# impulse.net
KiCad netlist of a schematic drawn in EAGLE
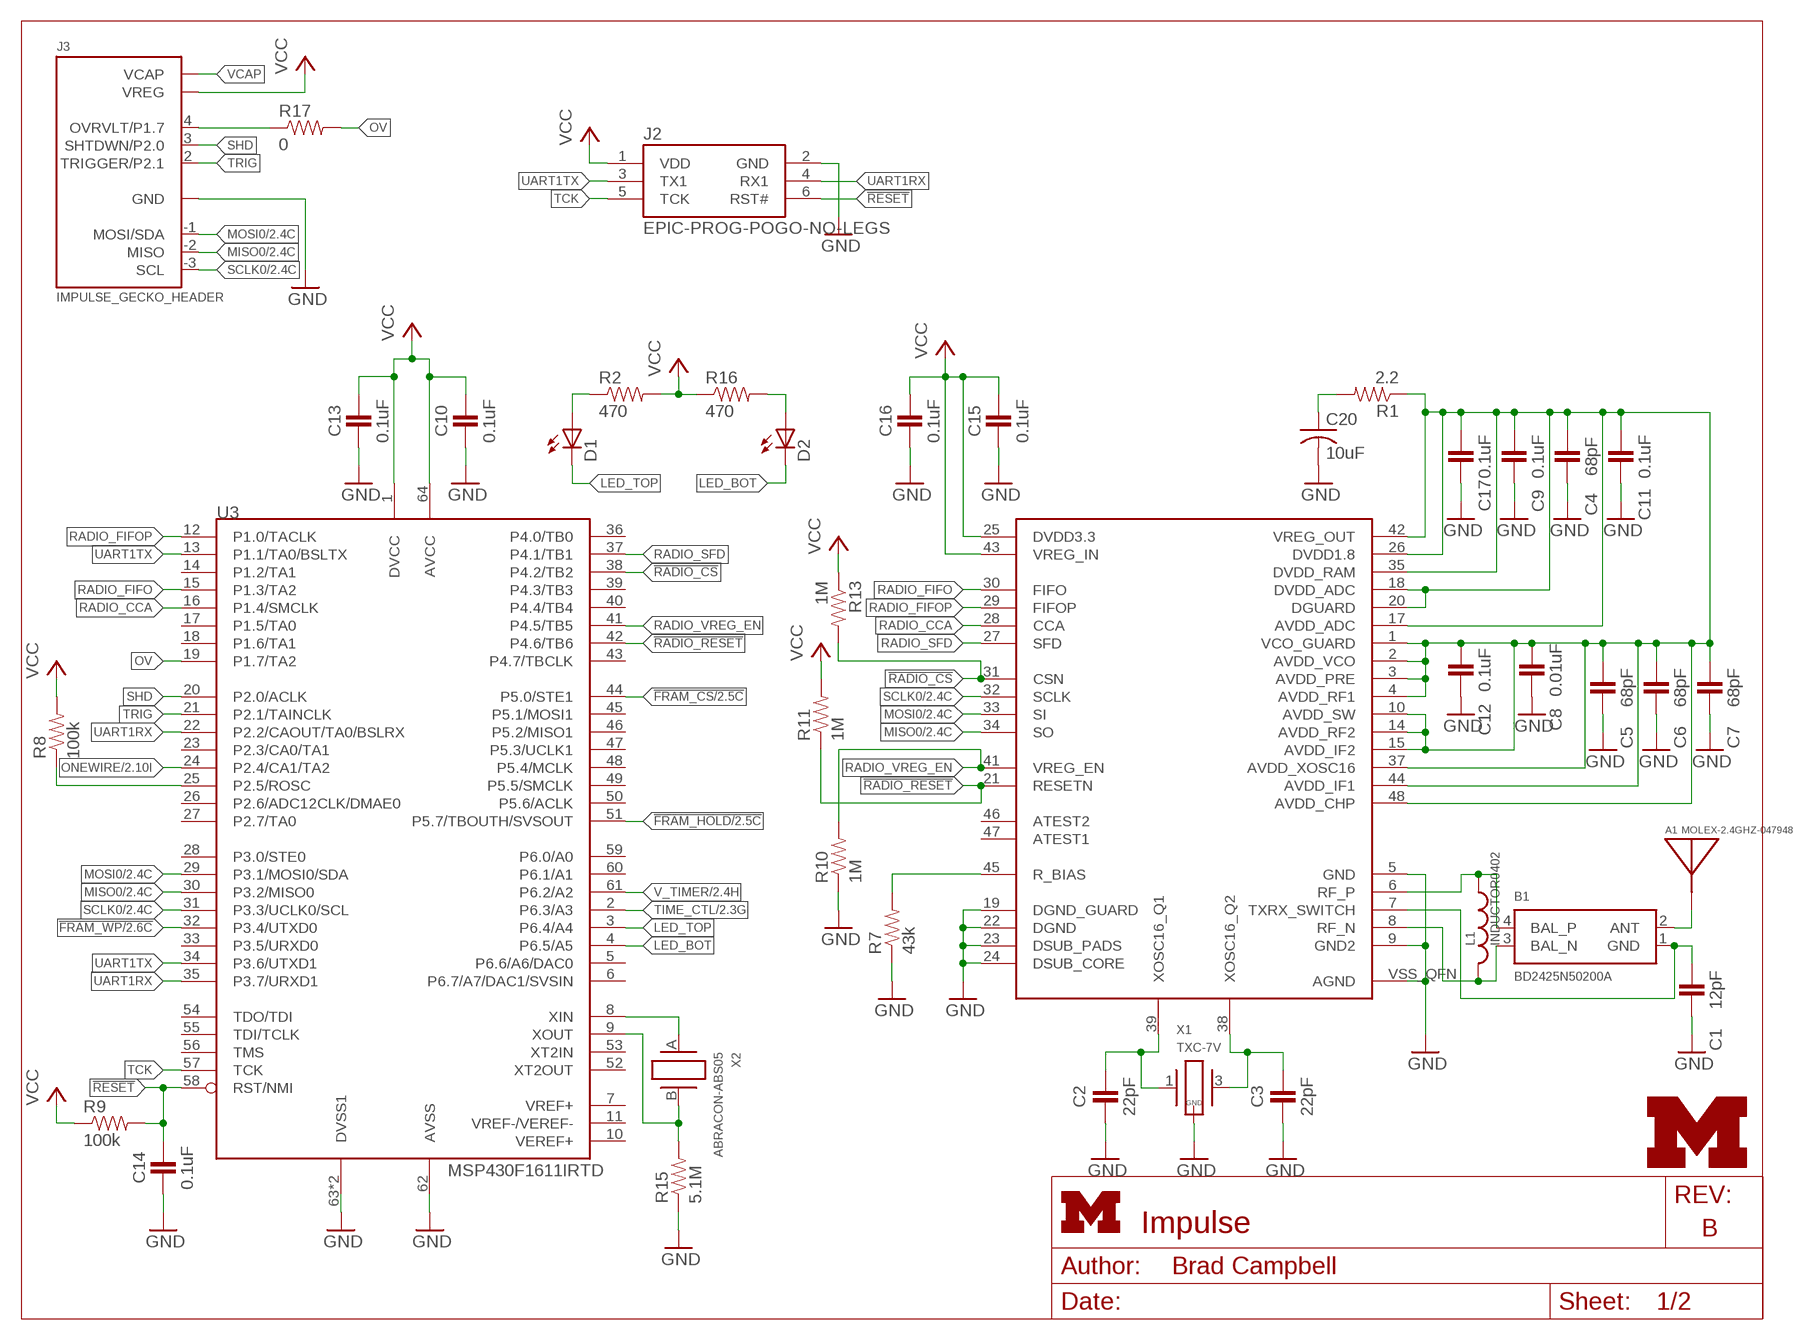
[diagram p0: schematic, sheet 1]
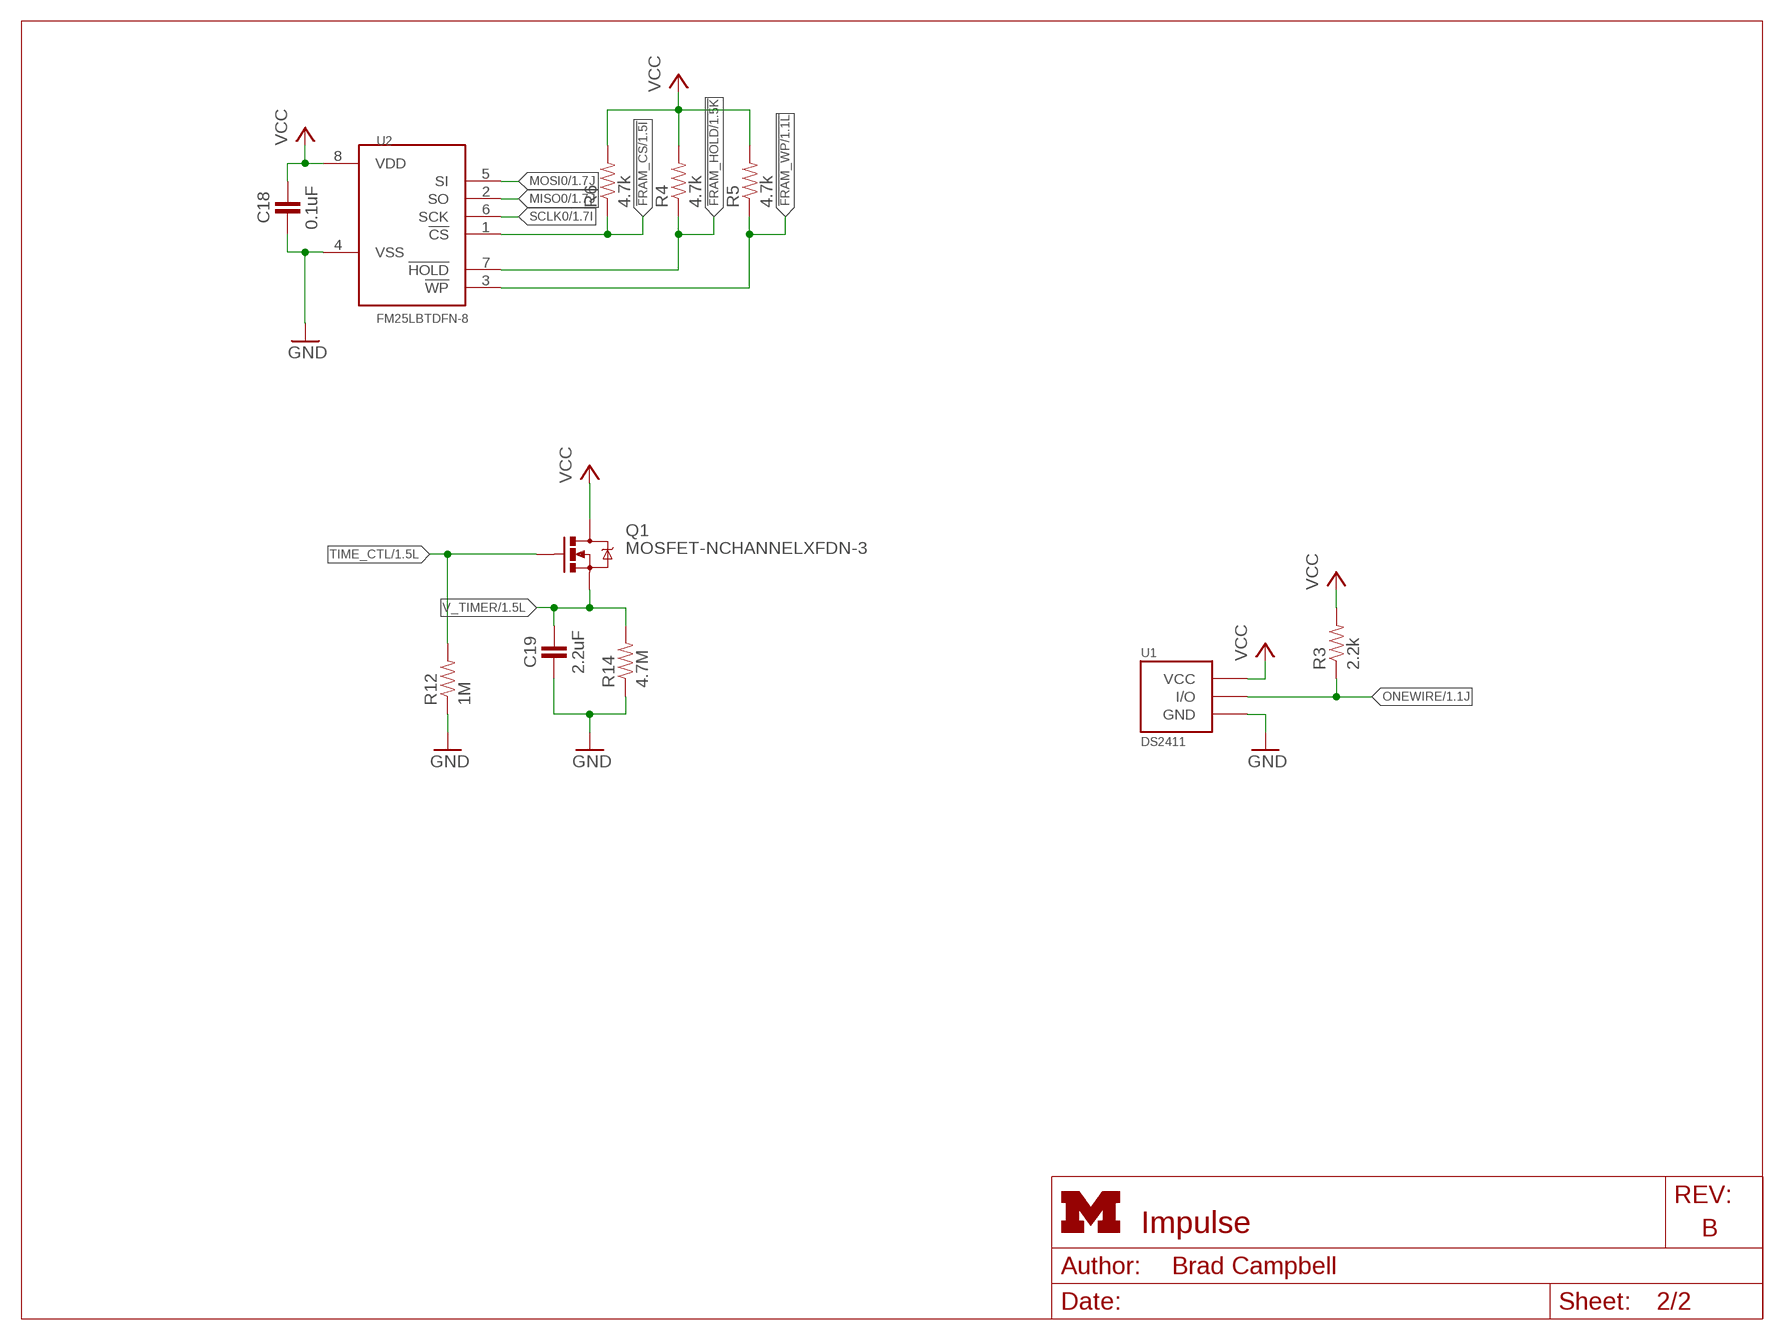
[diagram p1: schematic, sheet 2]

(export (version "E")
  (design (tool "Eeschema 10.0.6"))
  (components
    (comp (ref "C18")
      (value "0.1uF")
      (footprint "eagle-import:0402_CAP")
      (libsource (lib "eagle-import") (part "CAPACITOR"))
    )
    (comp (ref "C19")
      (value "2.2uF")
      (footprint "eagle-import:0402_CAP")
      (libsource (lib "eagle-import") (part "CAPACITOR"))
    )
    (comp (ref "Q1")
      (value "MOSFET-NCHANNELXFDN-3")
      (footprint "eagle-import:XFDFN-3")
      (libsource (lib "eagle-import") (part "MOSFET-NCHANNELXFDN-3"))
    )
    (comp (ref "R3")
      (value "2.2k")
      (footprint "eagle-import:0402_RES")
      (libsource (lib "eagle-import") (part "RESISTOR"))
    )
    (comp (ref "R4")
      (value "4.7k")
      (footprint "eagle-import:0402_RES")
      (libsource (lib "eagle-import") (part "RESISTOR"))
    )
    (comp (ref "R5")
      (value "4.7k")
      (footprint "eagle-import:0402_RES")
      (libsource (lib "eagle-import") (part "RESISTOR"))
    )
    (comp (ref "R6")
      (value "4.7k")
      (footprint "eagle-import:0402_RES")
      (libsource (lib "eagle-import") (part "RESISTOR"))
    )
    (comp (ref "R12")
      (value "1M")
      (footprint "eagle-import:0402_RES")
      (libsource (lib "eagle-import") (part "RESISTOR"))
    )
    (comp (ref "R14")
      (value "4.7M")
      (footprint "eagle-import:0402_RES")
      (libsource (lib "eagle-import") (part "RESISTOR"))
    )
    (comp (ref "U1")
      (value "DS2411")
      (footprint "eagle-import:SOT-23")
      (libsource (lib "eagle-import") (part "DS2411"))
    )
    (comp (ref "U2")
      (value "FM25LBTDFN-8")
      (footprint "eagle-import:TDFN-8")
      (libsource (lib "eagle-import") (part "FM25LBTDFN-8"))
    )
    (comp (ref "A1")
      (value "MOLEX-2.4GHZ-047948")
      (footprint "eagle-import:MOLEX-47948-ANTENNA")
      (libsource (lib "eagle-import") (part "MOLEX-2.4GHZ-047948"))
    )
    (comp (ref "B1")
      (value "BD2425N50200A")
      (footprint "eagle-import:BD2425N50200A")
      (libsource (lib "eagle-import") (part "BD2425N50200A"))
    )
    (comp (ref "C1")
      (value "12pF")
      (footprint "eagle-import:0402_CAP")
      (libsource (lib "eagle-import") (part "CAPACITOR"))
    )
    (comp (ref "C2")
      (value "22pF")
      (footprint "eagle-import:0402_CAP")
      (libsource (lib "eagle-import") (part "CAPACITOR"))
    )
    (comp (ref "C3")
      (value "22pF")
      (footprint "eagle-import:0402_CAP")
      (libsource (lib "eagle-import") (part "CAPACITOR"))
    )
    (comp (ref "C4")
      (value "68pF")
      (footprint "eagle-import:0402_CAP")
      (libsource (lib "eagle-import") (part "CAPACITOR"))
    )
    (comp (ref "C5")
      (value "68pF")
      (footprint "eagle-import:0402_CAP")
      (libsource (lib "eagle-import") (part "CAPACITOR"))
    )
    (comp (ref "C6")
      (value "68pF")
      (footprint "eagle-import:0402_CAP")
      (libsource (lib "eagle-import") (part "CAPACITOR"))
    )
    (comp (ref "C7")
      (value "68pF")
      (footprint "eagle-import:0402_CAP")
      (libsource (lib "eagle-import") (part "CAPACITOR"))
    )
    (comp (ref "C8")
      (value "0.01uF")
      (footprint "eagle-import:0402_CAP")
      (libsource (lib "eagle-import") (part "CAPACITOR"))
    )
    (comp (ref "C9")
      (value "0.1uF")
      (footprint "eagle-import:0402_CAP")
      (libsource (lib "eagle-import") (part "CAPACITOR"))
    )
    (comp (ref "C10")
      (value "0.1uF")
      (footprint "eagle-import:0402_CAP")
      (libsource (lib "eagle-import") (part "CAPACITOR"))
    )
    (comp (ref "C11")
      (value "0.1uF")
      (footprint "eagle-import:0402_CAP")
      (libsource (lib "eagle-import") (part "CAPACITOR"))
    )
    (comp (ref "C12")
      (value "0.1uF")
      (footprint "eagle-import:0402_CAP")
      (libsource (lib "eagle-import") (part "CAPACITOR"))
    )
    (comp (ref "C13")
      (value "0.1uF")
      (footprint "eagle-import:0402_CAP")
      (libsource (lib "eagle-import") (part "CAPACITOR"))
    )
    (comp (ref "C14")
      (value "0.1uF")
      (footprint "eagle-import:0402_CAP")
      (libsource (lib "eagle-import") (part "CAPACITOR"))
    )
    (comp (ref "C15")
      (value "0.1uF")
      (footprint "eagle-import:0402_CAP")
      (libsource (lib "eagle-import") (part "CAPACITOR"))
    )
    (comp (ref "C16")
      (value "0.1uF")
      (footprint "eagle-import:0402_CAP")
      (libsource (lib "eagle-import") (part "CAPACITOR"))
    )
    (comp (ref "C17")
      (value "0.1uF")
      (footprint "eagle-import:0402_CAP")
      (libsource (lib "eagle-import") (part "CAPACITOR"))
    )
    (comp (ref "C20")
      (value "10uF")
      (footprint "eagle-import:C0805")
      (libsource (lib "eagle-import") (part "C-USC0805"))
    )
    (comp (ref "D1")
      (value "LED0603")
      (footprint "eagle-import:LED-0603")
      (libsource (lib "eagle-import") (part "LED0603"))
    )
    (comp (ref "D2")
      (value "LED0603")
      (footprint "eagle-import:LED-0603")
      (libsource (lib "eagle-import") (part "LED0603"))
    )
    (comp (ref "J2")
      (value "EPIC-PROG-POGO-NO-LEGS")
      (footprint "eagle-import:TC2030-IDC-NL")
      (libsource (lib "eagle-import") (part "EPIC-PROG-POGO-NO-LEGS"))
    )
    (comp (ref "J3")
      (value "IMPULSE_GECKO_HEADER")
      (footprint "eagle-import:HEADER1X9_0.05IN")
      (libsource (lib "eagle-import") (part "IMPULSE_GECKO_HEADER"))
    )
    (comp (ref "L1")
      (value "INDUCTOR0402")
      (footprint "eagle-import:0402_CAP")
      (libsource (lib "eagle-import") (part "INDUCTOR0402"))
    )
    (comp (ref "R1")
      (value "2.2")
      (footprint "eagle-import:0402_RES")
      (libsource (lib "eagle-import") (part "RESISTOR"))
    )
    (comp (ref "R2")
      (value "470")
      (footprint "eagle-import:0402_RES")
      (libsource (lib "eagle-import") (part "RESISTOR"))
    )
    (comp (ref "R7")
      (value "43k")
      (footprint "eagle-import:0402_RES")
      (libsource (lib "eagle-import") (part "RESISTOR"))
    )
    (comp (ref "R8")
      (value "100k")
      (footprint "eagle-import:0402_RES")
      (libsource (lib "eagle-import") (part "RESISTOR"))
    )
    (comp (ref "R9")
      (value "100k")
      (footprint "eagle-import:0402_RES")
      (libsource (lib "eagle-import") (part "RESISTOR"))
    )
    (comp (ref "R10")
      (value "1M")
      (footprint "eagle-import:0402_RES")
      (libsource (lib "eagle-import") (part "RESISTOR"))
    )
    (comp (ref "R11")
      (value "1M")
      (footprint "eagle-import:0402_RES")
      (libsource (lib "eagle-import") (part "RESISTOR"))
    )
    (comp (ref "R13")
      (value "1M")
      (footprint "eagle-import:0402_RES")
      (libsource (lib "eagle-import") (part "RESISTOR"))
    )
    (comp (ref "R15")
      (value "5.1M")
      (footprint "eagle-import:0402_RES")
      (libsource (lib "eagle-import") (part "RESISTOR"))
    )
    (comp (ref "R16")
      (value "470")
      (footprint "eagle-import:0402_RES")
      (libsource (lib "eagle-import") (part "RESISTOR"))
    )
    (comp (ref "R17")
      (value "0")
      (footprint "eagle-import:0402_RES")
      (libsource (lib "eagle-import") (part "RESISTOR"))
    )
    (comp (ref "U$1")
      (value "UMICH_SOLID_SMALL")
      (footprint "eagle-import:UMICH_SOLID_75MIL")
      (libsource (lib "eagle-import") (part "UMICH_SOLID_SMALL"))
    )
    (comp (ref "U3")
      (value "MSP430F1611IRTD")
      (footprint "eagle-import:S-PVQFN-N64")
      (libsource (lib "eagle-import") (part "MSP430F1611IRTD"))
    )
    (comp (ref "U4")
      (value "CC2420RGZ")
      (footprint "eagle-import:S-PVQFN-N48")
      (libsource (lib "eagle-import") (part "CC2420RGZ"))
    )
    (comp (ref "X1")
      (value "TXC-7V")
      (footprint "eagle-import:TXC-7V")
      (libsource (lib "eagle-import") (part "TXC-7V"))
    )
    (comp (ref "X2")
      (value "ABRACON-ABS05")
      (footprint "eagle-import:ABS05")
      (libsource (lib "eagle-import") (part "ABRACON-ABS05"))
    )
  )
  (nets
    (net (code "1") (name "GND") (class "Default")
      (node (ref "C1") (pin "2") (pinfunction "2_2") (pintype "bidirectional"))
      (node (ref "C10") (pin "2") (pinfunction "2_2") (pintype "bidirectional"))
      (node (ref "C11") (pin "2") (pinfunction "2_2") (pintype "bidirectional"))
      (node (ref "C12") (pin "2") (pinfunction "2_2") (pintype "bidirectional"))
      (node (ref "C13") (pin "2") (pinfunction "2_2") (pintype "bidirectional"))
      (node (ref "C14") (pin "2") (pinfunction "2_2") (pintype "bidirectional"))
      (node (ref "C15") (pin "2") (pinfunction "2_2") (pintype "bidirectional"))
      (node (ref "C16") (pin "2") (pinfunction "2_2") (pintype "bidirectional"))
      (node (ref "C17") (pin "2") (pinfunction "2_2") (pintype "bidirectional"))
      (node (ref "C18") (pin "2") (pinfunction "2_2") (pintype "bidirectional"))
      (node (ref "C19") (pin "2") (pinfunction "2_2") (pintype "bidirectional"))
      (node (ref "C2") (pin "2") (pinfunction "2_2") (pintype "bidirectional"))
      (node (ref "C20") (pin "2") (pinfunction "2_2") (pintype "passive"))
      (node (ref "C3") (pin "2") (pinfunction "2_2") (pintype "bidirectional"))
      (node (ref "C4") (pin "2") (pinfunction "2_2") (pintype "bidirectional"))
      (node (ref "C5") (pin "2") (pinfunction "2_2") (pintype "bidirectional"))
      (node (ref "C6") (pin "2") (pinfunction "2_2") (pintype "bidirectional"))
      (node (ref "C7") (pin "2") (pinfunction "2_2") (pintype "bidirectional"))
      (node (ref "C8") (pin "2") (pinfunction "2_2") (pintype "bidirectional"))
      (node (ref "C9") (pin "2") (pinfunction "2_2") (pintype "bidirectional"))
      (node (ref "J2") (pin "2") (pinfunction "GND_2") (pintype "bidirectional"))
      (node (ref "J3") (pin "0") (pinfunction "GND_0") (pintype "bidirectional"))
      (node (ref "R10") (pin "1") (pinfunction "1_1") (pintype "passive"))
      (node (ref "R12") (pin "1") (pinfunction "1_1") (pintype "passive"))
      (node (ref "R14") (pin "1") (pinfunction "1_1") (pintype "passive"))
      (node (ref "R15") (pin "1") (pinfunction "1_1") (pintype "passive"))
      (node (ref "R7") (pin "1") (pinfunction "1_1") (pintype "passive"))
      (node (ref "U1") (pin "3") (pinfunction "GND_3") (pintype "bidirectional"))
      (node (ref "U2") (pin "4") (pinfunction "VSS_4") (pintype "bidirectional"))
      (node (ref "U3") (pin "62") (pinfunction "AVSS_62") (pintype "power_in"))
      (node (ref "U3") (pin "63") (pinfunction "DVSS1_63") (pintype "power_in"))
      (node (ref "U3") (pin "GND") (pinfunction "DVSS1_GND") (pintype "power_in"))
      (node (ref "U4") (pin "19") (pinfunction "DGND_GUARD_19") (pintype "bidirectional"))
      (node (ref "U4") (pin "22") (pinfunction "DGND_22") (pintype "bidirectional"))
      (node (ref "U4") (pin "23") (pinfunction "DSUB_PADS_23") (pintype "bidirectional"))
      (node (ref "U4") (pin "24") (pinfunction "DSUB_CORE_24") (pintype "bidirectional"))
      (node (ref "U4") (pin "5") (pinfunction "GND_5") (pintype "bidirectional"))
      (node (ref "U4") (pin "9") (pinfunction "GND2_9") (pintype "bidirectional"))
      (node (ref "U4") (pin "VSS_QFN") (pinfunction "AGND_VSS_QFN") (pintype "bidirectional"))
      (node (ref "X1") (pin "2") (pinfunction "GND_2") (pintype "bidirectional"))
      (node (ref "X1") (pin "4") (pinfunction "GND_4") (pintype "bidirectional"))
    )
    (net (code "2") (name "LED_BOT") (class "Default")
      (node (ref "D2") (pin "C") (pinfunction "C_C") (pintype "passive"))
      (node (ref "U3") (pin "4") (pinfunction "P6.5/A5_4") (pintype "bidirectional"))
    )
    (net (code "3") (name "LED_TOP") (class "Default")
      (node (ref "D1") (pin "C") (pinfunction "C_C") (pintype "passive"))
      (node (ref "U3") (pin "3") (pinfunction "P6.4/A4_3") (pintype "bidirectional"))
    )
    (net (code "4") (name "MISO0") (class "Default")
      (node (ref "J3") (pin "-2") (pinfunction "MISO_-2") (pintype "bidirectional"))
      (node (ref "U2") (pin "2") (pinfunction "SO_2") (pintype "bidirectional"))
      (node (ref "U3") (pin "30") (pinfunction "P3.2/MISO0_30") (pintype "bidirectional"))
      (node (ref "U4") (pin "34") (pinfunction "SO_34") (pintype "bidirectional"))
    )
    (net (code "5") (name "MOSI0") (class "Default")
      (node (ref "J3") (pin "-1") (pinfunction "MOSI/SDA_-1") (pintype "bidirectional"))
      (node (ref "U2") (pin "5") (pinfunction "SI_5") (pintype "bidirectional"))
      (node (ref "U3") (pin "29") (pinfunction "P3.1/MOSI0/SDA_29") (pintype "bidirectional"))
      (node (ref "U4") (pin "33") (pinfunction "SI_33") (pintype "bidirectional"))
    )
    (net (code "6") (name "Net-(A1-ANTENNA)") (class "Default")
      (node (ref "A1") (pin "1") (pinfunction "ANTENNA_1") (pintype "bidirectional"))
      (node (ref "B1") (pin "2") (pinfunction "ANT_2") (pintype "bidirectional"))
    )
    (net (code "7") (name "Net-(B1-BAL_N)") (class "Default")
      (node (ref "B1") (pin "3") (pinfunction "BAL_N_3") (pintype "bidirectional"))
      (node (ref "L1") (pin "2") (pinfunction "P$2_2") (pintype "bidirectional"))
      (node (ref "U4") (pin "8") (pinfunction "RF_N_8") (pintype "bidirectional"))
    )
    (net (code "8") (name "Net-(B1-BAL_P)") (class "Default")
      (node (ref "B1") (pin "4") (pinfunction "BAL_P_4") (pintype "bidirectional"))
      (node (ref "L1") (pin "1") (pinfunction "1_1") (pintype "bidirectional"))
      (node (ref "U4") (pin "6") (pinfunction "RF_P_6") (pintype "bidirectional"))
    )
    (net (code "9") (name "Net-(B1-GND)") (class "Default")
      (node (ref "B1") (pin "1") (pinfunction "GND_1") (pintype "bidirectional"))
      (node (ref "C1") (pin "1") (pinfunction "1_1") (pintype "bidirectional"))
      (node (ref "U4") (pin "7") (pinfunction "TXRX_SWITCH_7") (pintype "bidirectional"))
    )
    (net (code "10") (name "Net-(C20-Pad1)") (class "Default")
      (node (ref "C20") (pin "1") (pinfunction "1_1") (pintype "passive"))
      (node (ref "R1") (pin "2") (pinfunction "2_2") (pintype "passive"))
    )
    (net (code "11") (name "Net-(D1-PadA)") (class "Default")
      (node (ref "D1") (pin "A") (pinfunction "A_A") (pintype "passive"))
      (node (ref "R2") (pin "1") (pinfunction "1_1") (pintype "passive"))
    )
    (net (code "12") (name "Net-(D2-PadA)") (class "Default")
      (node (ref "D2") (pin "A") (pinfunction "A_A") (pintype "passive"))
      (node (ref "R16") (pin "2") (pinfunction "2_2") (pintype "passive"))
    )
    (net (code "13") (name "Net-(J3-OVRVLT{slash}P1.7)") (class "Default")
      (node (ref "J3") (pin "4") (pinfunction "OVRVLT/P1.7_4") (pintype "bidirectional"))
      (node (ref "R17") (pin "1") (pinfunction "1_1") (pintype "passive"))
    )
    (net (code "14") (name "Net-(U3-P2.5{slash}ROSC)") (class "Default")
      (node (ref "R8") (pin "1") (pinfunction "1_1") (pintype "passive"))
      (node (ref "U3") (pin "25") (pinfunction "P2.5/ROSC_25") (pintype "bidirectional"))
    )
    (net (code "15") (name "Net-(U3-XIN)") (class "Default")
      (node (ref "U3") (pin "8") (pinfunction "XIN_8") (pintype "bidirectional"))
      (node (ref "X2") (pin "A") (pinfunction "1_A") (pintype "bidirectional"))
    )
    (net (code "16") (name "Net-(U3-XOUT)") (class "Default")
      (node (ref "R15") (pin "2") (pinfunction "2_2") (pintype "passive"))
      (node (ref "U3") (pin "9") (pinfunction "XOUT_9") (pintype "bidirectional"))
      (node (ref "X2") (pin "B") (pinfunction "2_B") (pintype "bidirectional"))
    )
    (net (code "17") (name "Net-(U4-AVDD_ADC)") (class "Default")
      (node (ref "C11") (pin "1") (pinfunction "1_1") (pintype "bidirectional"))
      (node (ref "C12") (pin "1") (pinfunction "1_1") (pintype "bidirectional"))
      (node (ref "C17") (pin "1") (pinfunction "1_1") (pintype "bidirectional"))
      (node (ref "C4") (pin "1") (pinfunction "1_1") (pintype "bidirectional"))
      (node (ref "C5") (pin "1") (pinfunction "1_1") (pintype "bidirectional"))
      (node (ref "C6") (pin "1") (pinfunction "1_1") (pintype "bidirectional"))
      (node (ref "C7") (pin "1") (pinfunction "1_1") (pintype "bidirectional"))
      (node (ref "C8") (pin "1") (pinfunction "1_1") (pintype "bidirectional"))
      (node (ref "C9") (pin "1") (pinfunction "1_1") (pintype "bidirectional"))
      (node (ref "R1") (pin "1") (pinfunction "1_1") (pintype "passive"))
      (node (ref "U4") (pin "1") (pinfunction "VCO_GUARD_1") (pintype "bidirectional"))
      (node (ref "U4") (pin "10") (pinfunction "AVDD_SW_10") (pintype "bidirectional"))
      (node (ref "U4") (pin "14") (pinfunction "AVDD_RF2_14") (pintype "bidirectional"))
      (node (ref "U4") (pin "15") (pinfunction "AVDD_IF2_15") (pintype "bidirectional"))
      (node (ref "U4") (pin "17") (pinfunction "AVDD_ADC_17") (pintype "bidirectional"))
      (node (ref "U4") (pin "18") (pinfunction "DVDD_ADC_18") (pintype "bidirectional"))
      (node (ref "U4") (pin "2") (pinfunction "AVDD_VCO_2") (pintype "bidirectional"))
      (node (ref "U4") (pin "20") (pinfunction "DGUARD_20") (pintype "bidirectional"))
      (node (ref "U4") (pin "26") (pinfunction "DVDD1.8_26") (pintype "bidirectional"))
      (node (ref "U4") (pin "3") (pinfunction "AVDD_PRE_3") (pintype "bidirectional"))
      (node (ref "U4") (pin "35") (pinfunction "DVDD_RAM_35") (pintype "bidirectional"))
      (node (ref "U4") (pin "37") (pinfunction "AVDD_XOSC16_37") (pintype "bidirectional"))
      (node (ref "U4") (pin "4") (pinfunction "AVDD_RF1_4") (pintype "bidirectional"))
      (node (ref "U4") (pin "42") (pinfunction "VREG_OUT_42") (pintype "bidirectional"))
      (node (ref "U4") (pin "44") (pinfunction "AVDD_IF1_44") (pintype "bidirectional"))
      (node (ref "U4") (pin "48") (pinfunction "AVDD_CHP_48") (pintype "bidirectional"))
    )
    (net (code "18") (name "Net-(U4-R_BIAS)") (class "Default")
      (node (ref "R7") (pin "2") (pinfunction "2_2") (pintype "passive"))
      (node (ref "U4") (pin "45") (pinfunction "R_BIAS_45") (pintype "bidirectional"))
    )
    (net (code "19") (name "Net-(U4-XOSC16_Q1)") (class "Default")
      (node (ref "C2") (pin "1") (pinfunction "1_1") (pintype "bidirectional"))
      (node (ref "U4") (pin "39") (pinfunction "XOSC16_Q1_39") (pintype "bidirectional"))
      (node (ref "X1") (pin "1") (pinfunction "1_1") (pintype "bidirectional"))
    )
    (net (code "20") (name "Net-(U4-XOSC16_Q2)") (class "Default")
      (node (ref "C3") (pin "1") (pinfunction "1_1") (pintype "bidirectional"))
      (node (ref "U4") (pin "38") (pinfunction "XOSC16_Q2_38") (pintype "bidirectional"))
      (node (ref "X1") (pin "3") (pinfunction "2_3") (pintype "bidirectional"))
    )
    (net (code "21") (name "ONEWIRE") (class "Default")
      (node (ref "R3") (pin "1") (pinfunction "1_1") (pintype "passive"))
      (node (ref "U1") (pin "1") (pinfunction "I/O_1") (pintype "bidirectional"))
      (node (ref "U3") (pin "24") (pinfunction "P2.4/CA1/TA2_24") (pintype "bidirectional"))
    )
    (net (code "22") (name "OV") (class "Default")
      (node (ref "R17") (pin "2") (pinfunction "2_2") (pintype "passive"))
      (node (ref "U3") (pin "19") (pinfunction "P1.7/TA2_19") (pintype "bidirectional"))
    )
    (net (code "23") (name "RADIO_CCA") (class "Default")
      (node (ref "U3") (pin "16") (pinfunction "P1.4/SMCLK_16") (pintype "bidirectional"))
      (node (ref "U4") (pin "28") (pinfunction "CCA_28") (pintype "bidirectional"))
    )
    (net (code "24") (name "RADIO_FIFO") (class "Default")
      (node (ref "U3") (pin "15") (pinfunction "P1.3/TA2_15") (pintype "bidirectional"))
      (node (ref "U4") (pin "30") (pinfunction "FIFO_30") (pintype "bidirectional"))
    )
    (net (code "25") (name "RADIO_FIFOP") (class "Default")
      (node (ref "U3") (pin "12") (pinfunction "P1.0/TACLK_12") (pintype "bidirectional"))
      (node (ref "U4") (pin "29") (pinfunction "FIFOP_29") (pintype "bidirectional"))
    )
    (net (code "26") (name "RADIO_SFD") (class "Default")
      (node (ref "U3") (pin "37") (pinfunction "P4.1/TB1_37") (pintype "bidirectional"))
      (node (ref "U4") (pin "27") (pinfunction "SFD_27") (pintype "bidirectional"))
    )
    (net (code "27") (name "RADIO_VREG_EN") (class "Default")
      (node (ref "R10") (pin "2") (pinfunction "2_2") (pintype "passive"))
      (node (ref "U3") (pin "41") (pinfunction "P4.5/TB5_41") (pintype "bidirectional"))
      (node (ref "U4") (pin "41") (pinfunction "VREG_EN_41") (pintype "bidirectional"))
    )
    (net (code "28") (name "SCLK0") (class "Default")
      (node (ref "J3") (pin "-3") (pinfunction "SCL_-3") (pintype "bidirectional"))
      (node (ref "U2") (pin "6") (pinfunction "SCK_6") (pintype "bidirectional"))
      (node (ref "U3") (pin "31") (pinfunction "P3.3/UCLK0/SCL_31") (pintype "bidirectional"))
      (node (ref "U4") (pin "32") (pinfunction "SCLK_32") (pintype "bidirectional"))
    )
    (net (code "29") (name "SHD") (class "Default")
      (node (ref "J3") (pin "3") (pinfunction "SHTDWN/P2.0_3") (pintype "bidirectional"))
      (node (ref "U3") (pin "20") (pinfunction "P2.0/ACLK_20") (pintype "bidirectional"))
    )
    (net (code "30") (name "TCK") (class "Default")
      (node (ref "J2") (pin "5") (pinfunction "TCK_5") (pintype "bidirectional"))
      (node (ref "U3") (pin "57") (pinfunction "TCK_57") (pintype "bidirectional"))
    )
    (net (code "31") (name "TIME_CTL") (class "Default")
      (node (ref "Q1") (pin "G") (pinfunction "G_G") (pintype "passive"))
      (node (ref "R12") (pin "2") (pinfunction "2_2") (pintype "passive"))
      (node (ref "U3") (pin "2") (pinfunction "P6.3/A3_2") (pintype "bidirectional"))
    )
    (net (code "32") (name "TRIG") (class "Default")
      (node (ref "J3") (pin "2") (pinfunction "TRIGGER/P2.1_2") (pintype "bidirectional"))
      (node (ref "U3") (pin "21") (pinfunction "P2.1/TAINCLK_21") (pintype "bidirectional"))
    )
    (net (code "33") (name "UART1RX") (class "Default")
      (node (ref "J2") (pin "4") (pinfunction "RX1_4") (pintype "bidirectional"))
      (node (ref "U3") (pin "22") (pinfunction "P2.2/CAOUT/TA0/BSLRX_22") (pintype "bidirectional"))
      (node (ref "U3") (pin "35") (pinfunction "P3.7/URXD1_35") (pintype "bidirectional"))
    )
    (net (code "34") (name "UART1TX") (class "Default")
      (node (ref "J2") (pin "3") (pinfunction "TX1_3") (pintype "bidirectional"))
      (node (ref "U3") (pin "13") (pinfunction "P1.1/TA0/BSLTX_13") (pintype "bidirectional"))
      (node (ref "U3") (pin "34") (pinfunction "P3.6/UTXD1_34") (pintype "bidirectional"))
    )
    (net (code "35") (name "VCAP") (class "Default")
      (node (ref "J3") (pin "5") (pinfunction "VCAP_5") (pintype "output"))
    )
    (net (code "36") (name "VCC") (class "Default")
      (node (ref "C10") (pin "1") (pinfunction "1_1") (pintype "bidirectional"))
      (node (ref "C13") (pin "1") (pinfunction "1_1") (pintype "bidirectional"))
      (node (ref "C15") (pin "1") (pinfunction "1_1") (pintype "bidirectional"))
      (node (ref "C16") (pin "1") (pinfunction "1_1") (pintype "bidirectional"))
      (node (ref "C18") (pin "1") (pinfunction "1_1") (pintype "bidirectional"))
      (node (ref "J2") (pin "1") (pinfunction "VDD_1") (pintype "bidirectional"))
      (node (ref "J3") (pin "1") (pinfunction "VREG_1") (pintype "bidirectional"))
      (node (ref "Q1") (pin "D") (pinfunction "D_D") (pintype "passive"))
      (node (ref "R11") (pin "2") (pinfunction "2_2") (pintype "passive"))
      (node (ref "R13") (pin "1") (pinfunction "1_1") (pintype "passive"))
      (node (ref "R16") (pin "1") (pinfunction "1_1") (pintype "passive"))
      (node (ref "R2") (pin "2") (pinfunction "2_2") (pintype "passive"))
      (node (ref "R3") (pin "2") (pinfunction "2_2") (pintype "passive"))
      (node (ref "R4") (pin "2") (pinfunction "2_2") (pintype "passive"))
      (node (ref "R5") (pin "2") (pinfunction "2_2") (pintype "passive"))
      (node (ref "R6") (pin "2") (pinfunction "2_2") (pintype "passive"))
      (node (ref "R8") (pin "2") (pinfunction "2_2") (pintype "passive"))
      (node (ref "R9") (pin "1") (pinfunction "1_1") (pintype "passive"))
      (node (ref "U1") (pin "2") (pinfunction "VCC_2") (pintype "bidirectional"))
      (node (ref "U2") (pin "8") (pinfunction "VDD_8") (pintype "bidirectional"))
      (node (ref "U3") (pin "1") (pinfunction "DVCC_1") (pintype "power_in"))
      (node (ref "U3") (pin "64") (pinfunction "AVCC_64") (pintype "power_in"))
      (node (ref "U4") (pin "25") (pinfunction "DVDD3.3_25") (pintype "bidirectional"))
      (node (ref "U4") (pin "43") (pinfunction "VREG_IN_43") (pintype "bidirectional"))
    )
    (net (code "37") (name "V_TIMER") (class "Default")
      (node (ref "C19") (pin "1") (pinfunction "1_1") (pintype "bidirectional"))
      (node (ref "Q1") (pin "S") (pinfunction "S_S") (pintype "passive"))
      (node (ref "R14") (pin "2") (pinfunction "2_2") (pintype "passive"))
      (node (ref "U3") (pin "61") (pinfunction "P6.2/A2_61") (pintype "bidirectional"))
    )
    (net (code "38") (name "unconnected-(U3-P1.2{slash}TA1-Pad14)") (class "Default")
      (node (ref "U3") (pin "14") (pinfunction "P1.2/TA1_14") (pintype "bidirectional"))
    )
    (net (code "39") (name "unconnected-(U3-P1.5{slash}TA0-Pad17)") (class "Default")
      (node (ref "U3") (pin "17") (pinfunction "P1.5/TA0_17") (pintype "bidirectional"))
    )
    (net (code "40") (name "unconnected-(U3-P1.6{slash}TA1-Pad18)") (class "Default")
      (node (ref "U3") (pin "18") (pinfunction "P1.6/TA1_18") (pintype "bidirectional"))
    )
    (net (code "41") (name "unconnected-(U3-P2.3{slash}CA0{slash}TA1-Pad23)") (class "Default")
      (node (ref "U3") (pin "23") (pinfunction "P2.3/CA0/TA1_23") (pintype "bidirectional"))
    )
    (net (code "42") (name "unconnected-(U3-P2.6{slash}ADC12CLK{slash}DMAE0-Pad26)") (class "Default")
      (node (ref "U3") (pin "26") (pinfunction "P2.6/ADC12CLK/DMAE0_26") (pintype "bidirectional"))
    )
    (net (code "43") (name "unconnected-(U3-P2.7{slash}TA0-Pad27)") (class "Default")
      (node (ref "U3") (pin "27") (pinfunction "P2.7/TA0_27") (pintype "bidirectional"))
    )
    (net (code "44") (name "unconnected-(U3-P3.0{slash}STE0-Pad28)") (class "Default")
      (node (ref "U3") (pin "28") (pinfunction "P3.0/STE0_28") (pintype "bidirectional"))
    )
    (net (code "45") (name "unconnected-(U3-P3.5{slash}URXD0-Pad33)") (class "Default")
      (node (ref "U3") (pin "33") (pinfunction "P3.5/URXD0_33") (pintype "bidirectional"))
    )
    (net (code "46") (name "unconnected-(U3-P4.0{slash}TB0-Pad36)") (class "Default")
      (node (ref "U3") (pin "36") (pinfunction "P4.0/TB0_36") (pintype "bidirectional"))
    )
    (net (code "47") (name "unconnected-(U3-P4.3{slash}TB3-Pad39)") (class "Default")
      (node (ref "U3") (pin "39") (pinfunction "P4.3/TB3_39") (pintype "bidirectional"))
    )
    (net (code "48") (name "unconnected-(U3-P4.4{slash}TB4-Pad40)") (class "Default")
      (node (ref "U3") (pin "40") (pinfunction "P4.4/TB4_40") (pintype "bidirectional"))
    )
    (net (code "49") (name "unconnected-(U3-P4.7{slash}TBCLK-Pad43)") (class "Default")
      (node (ref "U3") (pin "43") (pinfunction "P4.7/TBCLK_43") (pintype "bidirectional"))
    )
    (net (code "50") (name "unconnected-(U3-P5.1{slash}MOSI1-Pad45)") (class "Default")
      (node (ref "U3") (pin "45") (pinfunction "P5.1/MOSI1_45") (pintype "bidirectional"))
    )
    (net (code "51") (name "unconnected-(U3-P5.2{slash}MISO1-Pad46)") (class "Default")
      (node (ref "U3") (pin "46") (pinfunction "P5.2/MISO1_46") (pintype "bidirectional"))
    )
    (net (code "52") (name "unconnected-(U3-P5.3{slash}UCLK1-Pad47)") (class "Default")
      (node (ref "U3") (pin "47") (pinfunction "P5.3/UCLK1_47") (pintype "bidirectional"))
    )
    (net (code "53") (name "unconnected-(U3-P5.4{slash}MCLK-Pad48)") (class "Default")
      (node (ref "U3") (pin "48") (pinfunction "P5.4/MCLK_48") (pintype "bidirectional"))
    )
    (net (code "54") (name "unconnected-(U3-P5.5{slash}SMCLK-Pad49)") (class "Default")
      (node (ref "U3") (pin "49") (pinfunction "P5.5/SMCLK_49") (pintype "bidirectional"))
    )
    (net (code "55") (name "unconnected-(U3-P5.6{slash}ACLK-Pad50)") (class "Default")
      (node (ref "U3") (pin "50") (pinfunction "P5.6/ACLK_50") (pintype "bidirectional"))
    )
    (net (code "56") (name "unconnected-(U3-P6.0{slash}A0-Pad59)") (class "Default")
      (node (ref "U3") (pin "59") (pinfunction "P6.0/A0_59") (pintype "bidirectional"))
    )
    (net (code "57") (name "unconnected-(U3-P6.1{slash}A1-Pad60)") (class "Default")
      (node (ref "U3") (pin "60") (pinfunction "P6.1/A1_60") (pintype "bidirectional"))
    )
    (net (code "58") (name "unconnected-(U3-P6.6{slash}A6{slash}DAC0-Pad5)") (class "Default")
      (node (ref "U3") (pin "5") (pinfunction "P6.6/A6/DAC0_5") (pintype "bidirectional"))
    )
    (net (code "59") (name "unconnected-(U3-P6.7{slash}A7{slash}DAC1{slash}SVSIN-Pad6)") (class "Default")
      (node (ref "U3") (pin "6") (pinfunction "P6.7/A7/DAC1/SVSIN_6") (pintype "bidirectional"))
    )
    (net (code "60") (name "unconnected-(U3-TDI{slash}TCLK-Pad55)") (class "Default")
      (node (ref "U3") (pin "55") (pinfunction "TDI/TCLK_55") (pintype "bidirectional"))
    )
    (net (code "61") (name "unconnected-(U3-TDO{slash}TDI-Pad54)") (class "Default")
      (node (ref "U3") (pin "54") (pinfunction "TDO/TDI_54") (pintype "bidirectional"))
    )
    (net (code "62") (name "unconnected-(U3-TMS-Pad56)") (class "Default")
      (node (ref "U3") (pin "56") (pinfunction "TMS_56") (pintype "bidirectional"))
    )
    (net (code "63") (name "unconnected-(U3-VEREF+-Pad10)") (class "Default")
      (node (ref "U3") (pin "10") (pinfunction "VEREF+_10") (pintype "bidirectional"))
    )
    (net (code "64") (name "unconnected-(U3-VREF+-Pad7)") (class "Default")
      (node (ref "U3") (pin "7") (pinfunction "VREF+_7") (pintype "bidirectional"))
    )
    (net (code "65") (name "unconnected-(U3-VREF-{slash}VEREF--Pad11)") (class "Default")
      (node (ref "U3") (pin "11") (pinfunction "VREF-/VEREF-_11") (pintype "bidirectional"))
    )
    (net (code "66") (name "unconnected-(U3-XT2IN-Pad53)") (class "Default")
      (node (ref "U3") (pin "53") (pinfunction "XT2IN_53") (pintype "bidirectional"))
    )
    (net (code "67") (name "unconnected-(U3-XT2OUT-Pad52)") (class "Default")
      (node (ref "U3") (pin "52") (pinfunction "XT2OUT_52") (pintype "bidirectional"))
    )
    (net (code "68") (name "unconnected-(U4-ATEST1-Pad47)") (class "Default")
      (node (ref "U4") (pin "47") (pinfunction "ATEST1_47") (pintype "bidirectional"))
    )
    (net (code "69") (name "unconnected-(U4-ATEST2-Pad46)") (class "Default")
      (node (ref "U4") (pin "46") (pinfunction "ATEST2_46") (pintype "bidirectional"))
    )
    (net (code "70") (name "~{FRAM_CS}") (class "Default")
      (node (ref "R6") (pin "1") (pinfunction "1_1") (pintype "passive"))
      (node (ref "U2") (pin "1") (pinfunction "~{CS}_1") (pintype "bidirectional"))
      (node (ref "U3") (pin "44") (pinfunction "P5.0/STE1_44") (pintype "bidirectional"))
    )
    (net (code "71") (name "~{FRAM_HOLD}") (class "Default")
      (node (ref "R4") (pin "1") (pinfunction "1_1") (pintype "passive"))
      (node (ref "U2") (pin "7") (pinfunction "~{HOLD}_7") (pintype "bidirectional"))
      (node (ref "U3") (pin "51") (pinfunction "P5.7/TBOUTH/SVSOUT_51") (pintype "bidirectional"))
    )
    (net (code "72") (name "~{FRAM_WP}") (class "Default")
      (node (ref "R5") (pin "1") (pinfunction "1_1") (pintype "passive"))
      (node (ref "U2") (pin "3") (pinfunction "~{WP}_3") (pintype "bidirectional"))
      (node (ref "U3") (pin "32") (pinfunction "P3.4/UTXD0_32") (pintype "bidirectional"))
    )
    (net (code "73") (name "~{RADIO_CS}") (class "Default")
      (node (ref "R13") (pin "2") (pinfunction "2_2") (pintype "passive"))
      (node (ref "U3") (pin "38") (pinfunction "P4.2/TB2_38") (pintype "bidirectional"))
      (node (ref "U4") (pin "31") (pinfunction "CSN_31") (pintype "bidirectional"))
    )
    (net (code "74") (name "~{RADIO_RESET}") (class "Default")
      (node (ref "R11") (pin "1") (pinfunction "1_1") (pintype "passive"))
      (node (ref "U3") (pin "42") (pinfunction "P4.6/TB6_42") (pintype "bidirectional"))
      (node (ref "U4") (pin "21") (pinfunction "RESETN_21") (pintype "bidirectional"))
    )
    (net (code "75") (name "~{RESET}") (class "Default")
      (node (ref "C14") (pin "1") (pinfunction "1_1") (pintype "bidirectional"))
      (node (ref "J2") (pin "6") (pinfunction "RST#_6") (pintype "bidirectional"))
      (node (ref "R9") (pin "2") (pinfunction "2_2") (pintype "passive"))
      (node (ref "U3") (pin "58") (pinfunction "RST/NMI_58") (pintype "bidirectional"))
    )
  )
)
